# Motherboard_Connectors_and_Memory.net
KiCad netlist of a schematic drawn in Altium Designer
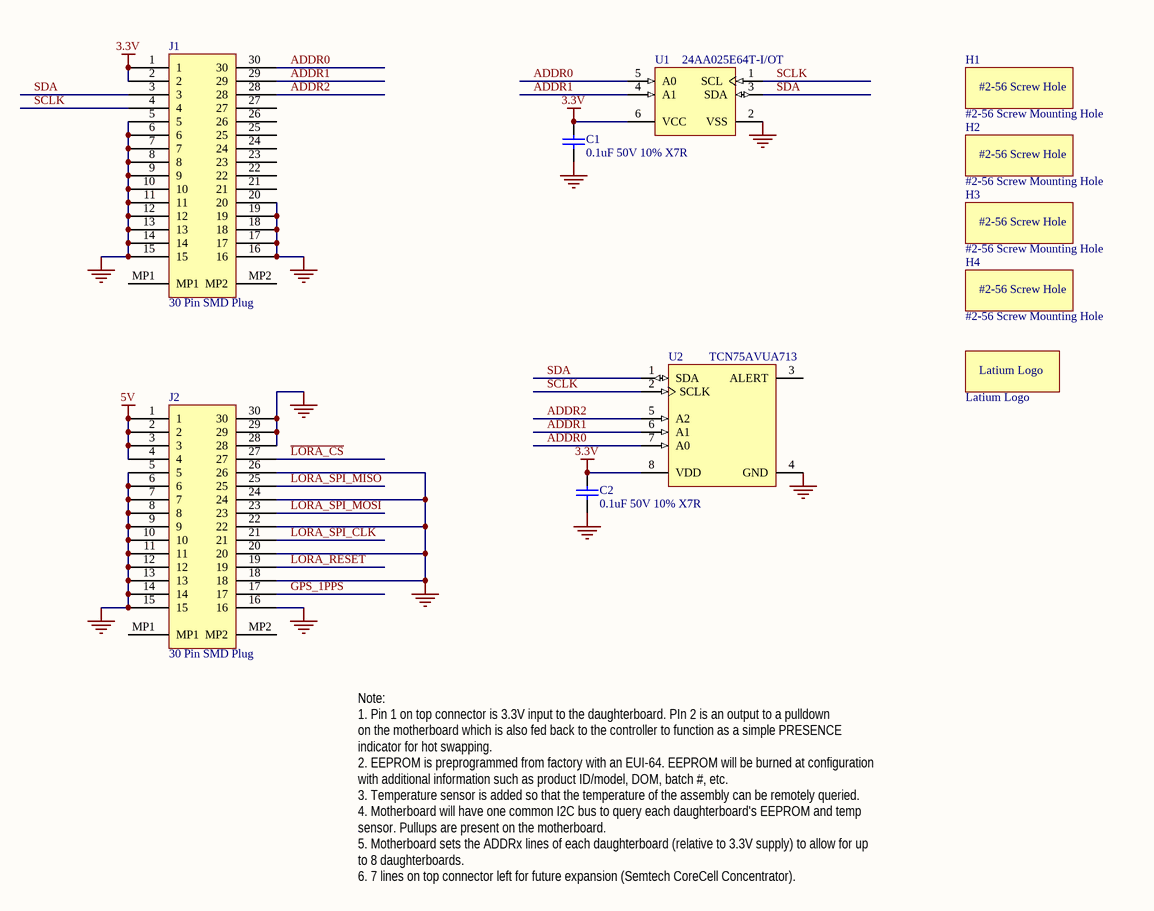
[diagram p0: Motherboard Connectors and Memory.SchDoc]

(export (version "E")
  (design (tool "Eeschema 10.0.6"))
  (components
    (comp (ref "C1")
      (value "0.1uF 50V 10% X7R")
      (footprint "CAPC1005L")
      (description "Capacitor")
      (libsource (lib "Miscellaneous Devices") (part "Cap"))
    )
    (comp (ref "C2")
      (value "0.1uF 50V 10% X7R")
      (footprint "CAPC1005L")
      (description "Capacitor")
      (libsource (lib "Miscellaneous Devices") (part "Cap"))
    )
    (comp (ref "H1")
      (value "#2-56 Screw Mounting Hole")
      (footprint "2-56 Screw Mount")
      (libsource (lib "Latium Component Library") (part "#2-56 Screw Support"))
    )
    (comp (ref "H2")
      (value "#2-56 Screw Mounting Hole")
      (footprint "2-56 Screw Mount")
      (libsource (lib "Latium Component Library") (part "#2-56 Screw Support"))
    )
    (comp (ref "H3")
      (value "#2-56 Screw Mounting Hole")
      (footprint "2-56 Screw Mount")
      (libsource (lib "Latium Component Library") (part "#2-56 Screw Support"))
    )
    (comp (ref "H4")
      (value "#2-56 Screw Mounting Hole")
      (footprint "2-56 Screw Mount")
      (libsource (lib "Latium Component Library") (part "#2-56 Screw Support"))
    )
    (comp (ref "H7")
      (value "Latium Logo")
      (footprint "LatiumLogo")
      (libsource (lib "Latium Component Library") (part "Latium Logo"))
    )
    (comp (ref "J1")
      (value "30 Pin SMD Plug")
      (footprint "10132797-031100LF")
      (description "CONN PLUG 30POS SMD GOLD")
      (fields
        (field (name "MANUFACTURER") "Amphenol ICC (FCI)")
        (field (name "MANUFACTURER PART NUMBER") "10132797-031100LF")
      )
      (libsource (lib "Latium Component Library") (part "Amphenol 30 Pos BergStak Plug"))
    )
    (comp (ref "J2")
      (value "30 Pin SMD Plug")
      (footprint "10132797-031100LF")
      (description "CONN PLUG 30POS SMD GOLD")
      (fields
        (field (name "MANUFACTURER") "Amphenol ICC (FCI)")
        (field (name "MANUFACTURER PART NUMBER") "10132797-031100LF")
      )
      (libsource (lib "Latium Component Library") (part "Amphenol 30 Pos BergStak Plug"))
    )
    (comp (ref "U1")
      (value "24AA025E64T-I/OT")
      (footprint "MCHP-SOT-23-OT6_L")
      (description "IC EEPROM 2K I2C 400KHZ SOT23-6")
      (fields (field (name "MANUFACTURER") "Microchip Technology"))
      (libsource (lib "Microchip I2C Serial EEPROM") (part "24AA025E64T-I/OT"))
    )
    (comp (ref "U2")
      (value "TCN75AVUA713")
      (footprint "MSOP-UA8_L")
      (description "SENSOR DIGITAL -40C-125C 8MSOP")
      (fields (field (name "MANUFACTURER") "Microchip Technology"))
      (libsource (lib "Microchip Thermal Management") (part "TCN75AVUA713"))
    )
  )
  (nets
    (net (code "1") (name "/ADDR0") (class "Default")
      (node (ref "J1") (pin "30") (pinfunction "30_30") (pintype "passive"))
      (node (ref "U1") (pin "5") (pinfunction "A0_5") (pintype "input"))
      (node (ref "U2") (pin "7") (pinfunction "A0_7") (pintype "input"))
    )
    (net (code "2") (name "/ADDR1") (class "Default")
      (node (ref "J1") (pin "29") (pinfunction "29_29") (pintype "passive"))
      (node (ref "U1") (pin "4") (pinfunction "A1_4") (pintype "input"))
      (node (ref "U2") (pin "6") (pinfunction "A1_6") (pintype "input"))
    )
    (net (code "3") (name "/ADDR2") (class "Default")
      (node (ref "J1") (pin "28") (pinfunction "28_28") (pintype "passive"))
      (node (ref "U2") (pin "5") (pinfunction "A2_5") (pintype "input"))
    )
    (net (code "4") (name "/GPS_1PPS") (class "Default")
      (node (ref "J2") (pin "17") (pinfunction "17_17") (pintype "passive"))
    )
    (net (code "5") (name "/LORA_RESET") (class "Default")
      (node (ref "J2") (pin "19") (pinfunction "19_19") (pintype "passive"))
    )
    (net (code "6") (name "/LORA_SPI_CLK") (class "Default")
      (node (ref "J2") (pin "21") (pinfunction "21_21") (pintype "passive"))
    )
    (net (code "7") (name "/LORA_SPI_MISO") (class "Default")
      (node (ref "J2") (pin "25") (pinfunction "25_25") (pintype "passive"))
    )
    (net (code "8") (name "/LORA_SPI_MOSI") (class "Default")
      (node (ref "J2") (pin "23") (pinfunction "23_23") (pintype "passive"))
    )
    (net (code "9") (name "/SCLK") (class "Default")
      (node (ref "J1") (pin "4") (pinfunction "4_4") (pintype "passive"))
      (node (ref "U1") (pin "1") (pinfunction "SCL_1") (pintype "input"))
      (node (ref "U2") (pin "2") (pinfunction "SCLK_2") (pintype "input"))
    )
    (net (code "10") (name "/SDA") (class "Default")
      (node (ref "J1") (pin "3") (pinfunction "3_3") (pintype "passive"))
      (node (ref "U1") (pin "3") (pinfunction "SDA_3") (pintype "bidirectional"))
      (node (ref "U2") (pin "1") (pinfunction "SDA_1") (pintype "bidirectional"))
    )
    (net (code "11") (name "/~{LORA_CS}") (class "Default")
      (node (ref "J2") (pin "27") (pinfunction "27_27") (pintype "passive"))
    )
    (net (code "12") (name "3.3V") (class "Default")
      (node (ref "C1") (pin "1") (pinfunction "1_1") (pintype "passive"))
      (node (ref "C2") (pin "1") (pinfunction "1_1") (pintype "passive"))
      (node (ref "J1") (pin "1") (pinfunction "1_1") (pintype "passive"))
      (node (ref "J1") (pin "2") (pinfunction "2_2") (pintype "passive"))
      (node (ref "U1") (pin "6") (pinfunction "VCC_6") (pintype "power_in"))
      (node (ref "U2") (pin "8") (pinfunction "VDD_8") (pintype "power_in"))
    )
    (net (code "13") (name "5V") (class "Default")
      (node (ref "J2") (pin "1") (pinfunction "1_1") (pintype "passive"))
      (node (ref "J2") (pin "2") (pinfunction "2_2") (pintype "passive"))
      (node (ref "J2") (pin "3") (pinfunction "3_3") (pintype "passive"))
      (node (ref "J2") (pin "4") (pinfunction "4_4") (pintype "passive"))
    )
    (net (code "14") (name "GND") (class "Default")
      (node (ref "C1") (pin "2") (pinfunction "2_2") (pintype "passive"))
      (node (ref "C2") (pin "2") (pinfunction "2_2") (pintype "passive"))
      (node (ref "J1") (pin "10") (pinfunction "10_10") (pintype "passive"))
      (node (ref "J1") (pin "11") (pinfunction "11_11") (pintype "passive"))
      (node (ref "J1") (pin "12") (pinfunction "12_12") (pintype "passive"))
      (node (ref "J1") (pin "13") (pinfunction "13_13") (pintype "passive"))
      (node (ref "J1") (pin "14") (pinfunction "14_14") (pintype "passive"))
      (node (ref "J1") (pin "15") (pinfunction "15_15") (pintype "passive"))
      (node (ref "J1") (pin "16") (pinfunction "16_16") (pintype "passive"))
      (node (ref "J1") (pin "17") (pinfunction "17_17") (pintype "passive"))
      (node (ref "J1") (pin "18") (pinfunction "18_18") (pintype "passive"))
      (node (ref "J1") (pin "19") (pinfunction "19_19") (pintype "passive"))
      (node (ref "J1") (pin "20") (pinfunction "20_20") (pintype "passive"))
      (node (ref "J1") (pin "5") (pinfunction "5_5") (pintype "passive"))
      (node (ref "J1") (pin "6") (pinfunction "6_6") (pintype "passive"))
      (node (ref "J1") (pin "7") (pinfunction "7_7") (pintype "passive"))
      (node (ref "J1") (pin "8") (pinfunction "8_8") (pintype "passive"))
      (node (ref "J1") (pin "9") (pinfunction "9_9") (pintype "passive"))
      (node (ref "J2") (pin "10") (pinfunction "10_10") (pintype "passive"))
      (node (ref "J2") (pin "11") (pinfunction "11_11") (pintype "passive"))
      (node (ref "J2") (pin "12") (pinfunction "12_12") (pintype "passive"))
      (node (ref "J2") (pin "13") (pinfunction "13_13") (pintype "passive"))
      (node (ref "J2") (pin "14") (pinfunction "14_14") (pintype "passive"))
      (node (ref "J2") (pin "15") (pinfunction "15_15") (pintype "passive"))
      (node (ref "J2") (pin "16") (pinfunction "16_16") (pintype "passive"))
      (node (ref "J2") (pin "18") (pinfunction "18_18") (pintype "passive"))
      (node (ref "J2") (pin "20") (pinfunction "20_20") (pintype "passive"))
      (node (ref "J2") (pin "22") (pinfunction "22_22") (pintype "passive"))
      (node (ref "J2") (pin "24") (pinfunction "24_24") (pintype "passive"))
      (node (ref "J2") (pin "26") (pinfunction "26_26") (pintype "passive"))
      (node (ref "J2") (pin "28") (pinfunction "28_28") (pintype "passive"))
      (node (ref "J2") (pin "29") (pinfunction "29_29") (pintype "passive"))
      (node (ref "J2") (pin "30") (pinfunction "30_30") (pintype "passive"))
      (node (ref "J2") (pin "5") (pinfunction "5_5") (pintype "passive"))
      (node (ref "J2") (pin "6") (pinfunction "6_6") (pintype "passive"))
      (node (ref "J2") (pin "7") (pinfunction "7_7") (pintype "passive"))
      (node (ref "J2") (pin "8") (pinfunction "8_8") (pintype "passive"))
      (node (ref "J2") (pin "9") (pinfunction "9_9") (pintype "passive"))
      (node (ref "U1") (pin "2") (pinfunction "VSS_2") (pintype "power_in"))
      (node (ref "U2") (pin "4") (pinfunction "GND_4") (pintype "power_in"))
    )
    (net (code "15") (name "unconnected-(J1-Pad21)") (class "Default")
      (node (ref "J1") (pin "21") (pinfunction "21_21") (pintype "passive"))
    )
    (net (code "16") (name "unconnected-(J1-Pad22)") (class "Default")
      (node (ref "J1") (pin "22") (pinfunction "22_22") (pintype "passive"))
    )
    (net (code "17") (name "unconnected-(J1-Pad23)") (class "Default")
      (node (ref "J1") (pin "23") (pinfunction "23_23") (pintype "passive"))
    )
    (net (code "18") (name "unconnected-(J1-Pad24)") (class "Default")
      (node (ref "J1") (pin "24") (pinfunction "24_24") (pintype "passive"))
    )
    (net (code "19") (name "unconnected-(J1-Pad25)") (class "Default")
      (node (ref "J1") (pin "25") (pinfunction "25_25") (pintype "passive"))
    )
    (net (code "20") (name "unconnected-(J1-Pad26)") (class "Default")
      (node (ref "J1") (pin "26") (pinfunction "26_26") (pintype "passive"))
    )
    (net (code "21") (name "unconnected-(J1-Pad27)") (class "Default")
      (node (ref "J1") (pin "27") (pinfunction "27_27") (pintype "passive"))
    )
    (net (code "22") (name "unconnected-(J1-PadMP1)") (class "Default")
      (node (ref "J1") (pin "MP1") (pinfunction "MP1_MP1") (pintype "passive"))
    )
    (net (code "23") (name "unconnected-(J1-PadMP2)") (class "Default")
      (node (ref "J1") (pin "MP2") (pinfunction "MP2_MP2") (pintype "passive"))
    )
    (net (code "24") (name "unconnected-(J2-PadMP1)") (class "Default")
      (node (ref "J2") (pin "MP1") (pinfunction "MP1_MP1") (pintype "passive"))
    )
    (net (code "25") (name "unconnected-(J2-PadMP2)") (class "Default")
      (node (ref "J2") (pin "MP2") (pinfunction "MP2_MP2") (pintype "passive"))
    )
    (net (code "26") (name "unconnected-(U2-ALERT-Pad3)") (class "Default")
      (node (ref "U2") (pin "3") (pinfunction "ALERT_3") (pintype "open_collector"))
    )
  )
)
